# SNES_DRONE_LEVEL_SHIFTER_1.net
KiCad netlist of a schematic drawn in Altium Designer
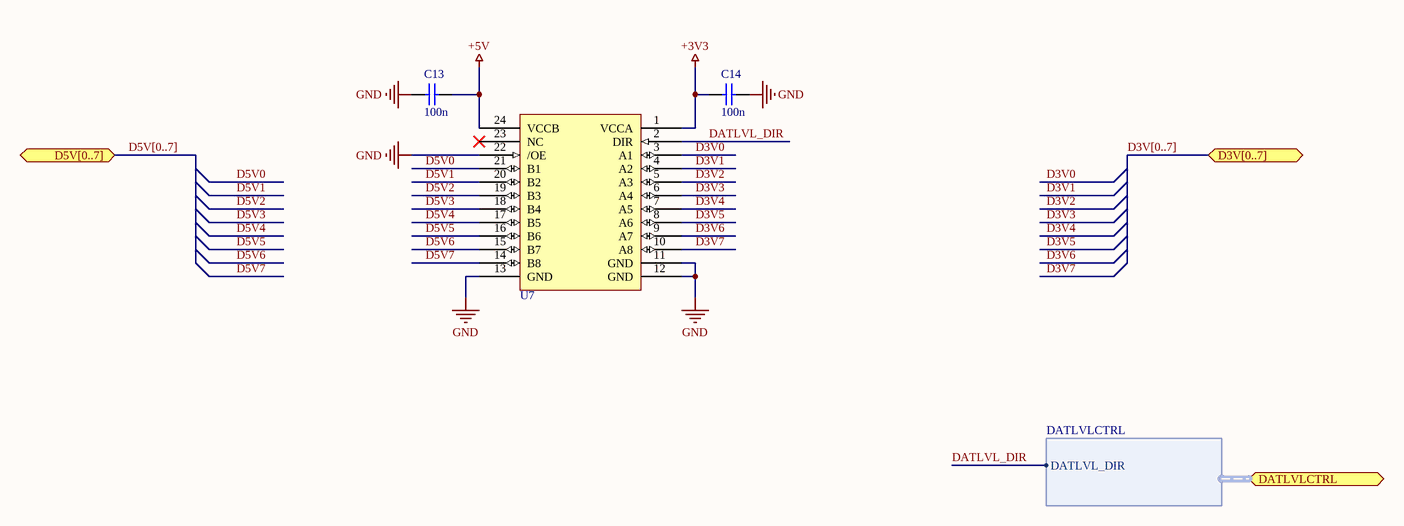
[diagram p0: SNES_DRONE_LEVEL_SHIFTER_1.SchDoc]

(export (version "E")
  (design (tool "Eeschema 10.0.6"))
  (components
    (comp (ref "C13")
      (value "100n")
      (footprint "cap_0603")
      (description "Capacitor")
      (fields (field (name "Comment") "cap_0603"))
      (libsource (lib "mycomponents") (part "cap_0603"))
    )
    (comp (ref "C14")
      (value "100n")
      (footprint "cap_0603")
      (description "Capacitor")
      (fields (field (name "Comment") "cap_0603"))
      (libsource (lib "mycomponents") (part "cap_0603"))
    )
    (comp (ref "U7")
      (value "IC_SN74LVCC3245APWR")
      (footprint "TSSOP24")
      (description "Bus-Transceiver, Produktreihe LVC, 8 Eingänge, 50mA, 7ns, 2.3V bis 5.5V, TSSOP 24")
      (libsource (lib "mycomponents") (part "IC_SN74LVCC3245APWR"))
    )
  )
  (nets
    (net (code "2") (name "+3V3") (class "Default")
      (node (ref "C14") (pin "2") (pinfunction "2_2") (pintype "passive"))
      (node (ref "U7") (pin "1") (pinfunction "VCCA_1") (pintype "power_in"))
    )
    (net (code "3") (name "+5V") (class "Default")
      (node (ref "C13") (pin "1") (pinfunction "1_1") (pintype "passive"))
      (node (ref "U7") (pin "24") (pinfunction "VCCB_24") (pintype "power_in"))
    )
    (net (code "4") (name "/D3V0") (class "Default")
      (node (ref "U7") (pin "3") (pinfunction "A1_3") (pintype "bidirectional"))
    )
    (net (code "5") (name "/D3V1") (class "Default")
      (node (ref "U7") (pin "4") (pinfunction "A2_4") (pintype "bidirectional"))
    )
    (net (code "6") (name "/D3V2") (class "Default")
      (node (ref "U7") (pin "5") (pinfunction "A3_5") (pintype "bidirectional"))
    )
    (net (code "7") (name "/D3V3") (class "Default")
      (node (ref "U7") (pin "6") (pinfunction "A4_6") (pintype "bidirectional"))
    )
    (net (code "8") (name "/D3V4") (class "Default")
      (node (ref "U7") (pin "7") (pinfunction "A5_7") (pintype "bidirectional"))
    )
    (net (code "9") (name "/D3V5") (class "Default")
      (node (ref "U7") (pin "8") (pinfunction "A6_8") (pintype "bidirectional"))
    )
    (net (code "10") (name "/D3V6") (class "Default")
      (node (ref "U7") (pin "9") (pinfunction "A7_9") (pintype "bidirectional"))
    )
    (net (code "11") (name "/D3V7") (class "Default")
      (node (ref "U7") (pin "10") (pinfunction "A8_10") (pintype "bidirectional"))
    )
    (net (code "13") (name "/D5V0") (class "Default")
      (node (ref "U7") (pin "21") (pinfunction "B1_21") (pintype "bidirectional"))
    )
    (net (code "14") (name "/D5V1") (class "Default")
      (node (ref "U7") (pin "20") (pinfunction "B2_20") (pintype "bidirectional"))
    )
    (net (code "15") (name "/D5V2") (class "Default")
      (node (ref "U7") (pin "19") (pinfunction "B3_19") (pintype "bidirectional"))
    )
    (net (code "16") (name "/D5V3") (class "Default")
      (node (ref "U7") (pin "18") (pinfunction "B4_18") (pintype "bidirectional"))
    )
    (net (code "17") (name "/D5V4") (class "Default")
      (node (ref "U7") (pin "17") (pinfunction "B5_17") (pintype "bidirectional"))
    )
    (net (code "18") (name "/D5V5") (class "Default")
      (node (ref "U7") (pin "16") (pinfunction "B6_16") (pintype "bidirectional"))
    )
    (net (code "19") (name "/D5V6") (class "Default")
      (node (ref "U7") (pin "15") (pinfunction "B7_15") (pintype "bidirectional"))
    )
    (net (code "20") (name "/D5V7") (class "Default")
      (node (ref "U7") (pin "14") (pinfunction "B8_14") (pintype "bidirectional"))
    )
    (net (code "22") (name "/DATLVL_DIR") (class "Default")
      (node (ref "U7") (pin "2") (pinfunction "DIR_2") (pintype "input"))
    )
    (net (code "24") (name "GND") (class "Default")
      (node (ref "C13") (pin "2") (pinfunction "2_2") (pintype "passive"))
      (node (ref "C14") (pin "1") (pinfunction "1_1") (pintype "passive"))
      (node (ref "U7") (pin "11") (pinfunction "GND_11") (pintype "power_in"))
      (node (ref "U7") (pin "12") (pinfunction "GND_12") (pintype "power_in"))
      (node (ref "U7") (pin "13") (pinfunction "GND_13") (pintype "power_in"))
      (node (ref "U7") (pin "22") (pinfunction "/OE_22") (pintype "input"))
    )
    (net (code "25") (name "unconnected-(U7-NC-Pad23)") (class "Default")
      (node (ref "U7") (pin "23") (pinfunction "NC_23") (pintype "passive+no_connect"))
    )
  )
)
